# PC.net
KiCad netlist of a schematic drawn in EAGLE
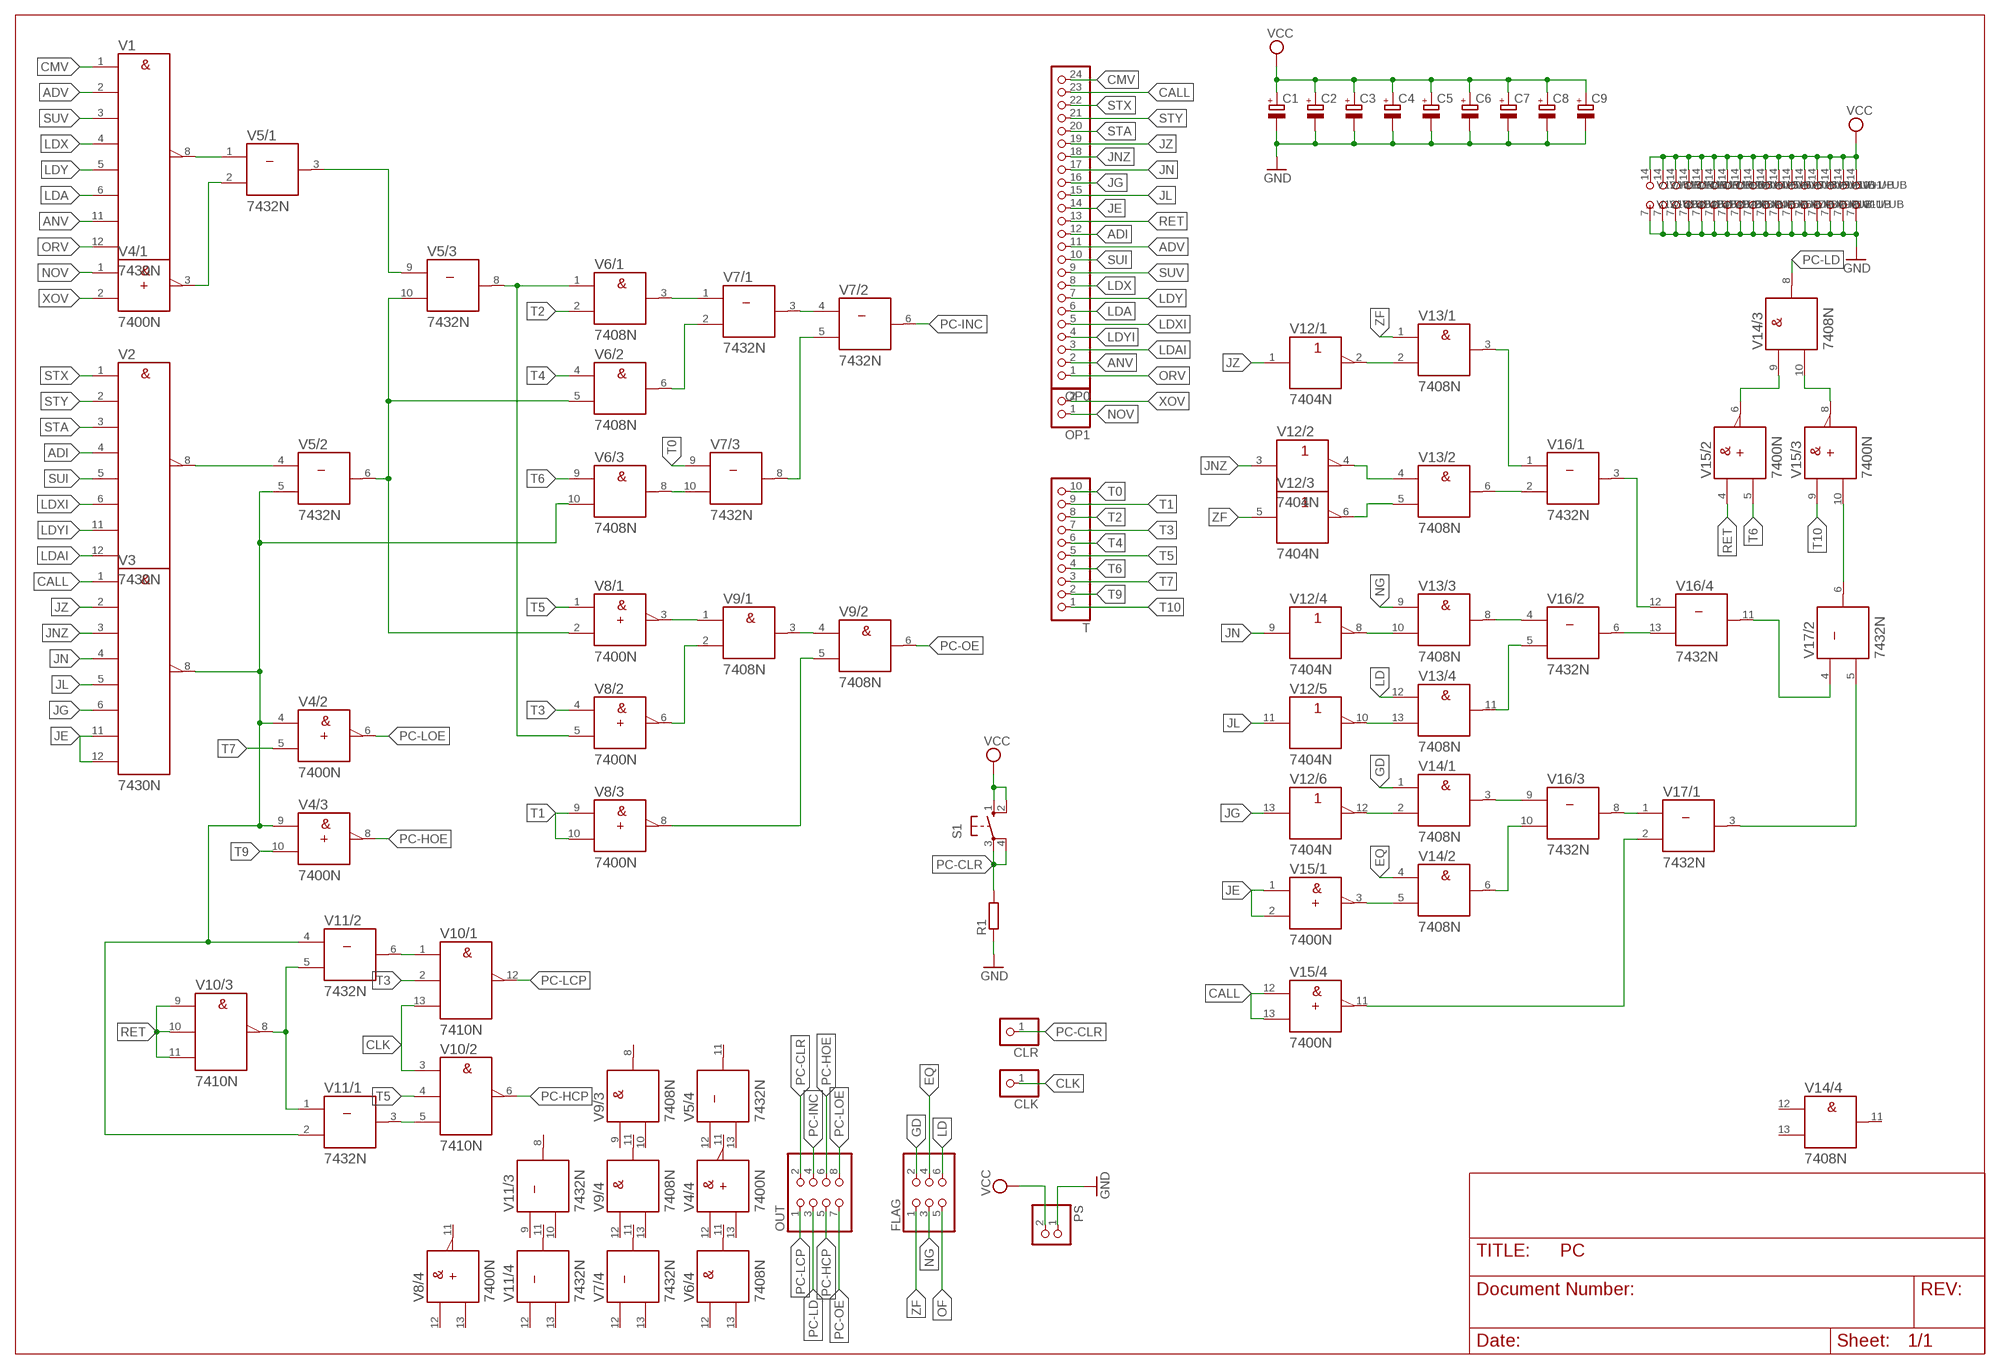
[diagram p0: schematic, sheet 1]

(export (version "E")
  (design (tool "Eeschema 10.0.6"))
  (components
    (comp (ref "C1")
      (value "CPOL-EUE2.5-6")
      (footprint "eagle-import:E2,5-6")
      (libsource (lib "eagle-import") (part "CPOL-EUE2.5-6"))
    )
    (comp (ref "C2")
      (value "CPOL-EUE2.5-6")
      (footprint "eagle-import:E2,5-6")
      (libsource (lib "eagle-import") (part "CPOL-EUE2.5-6"))
    )
    (comp (ref "C3")
      (value "CPOL-EUE2.5-6")
      (footprint "eagle-import:E2,5-6")
      (libsource (lib "eagle-import") (part "CPOL-EUE2.5-6"))
    )
    (comp (ref "C4")
      (value "CPOL-EUE2.5-6")
      (footprint "eagle-import:E2,5-6")
      (libsource (lib "eagle-import") (part "CPOL-EUE2.5-6"))
    )
    (comp (ref "C5")
      (value "CPOL-EUE2.5-6")
      (footprint "eagle-import:E2,5-6")
      (libsource (lib "eagle-import") (part "CPOL-EUE2.5-6"))
    )
    (comp (ref "C6")
      (value "CPOL-EUE2.5-6")
      (footprint "eagle-import:E2,5-6")
      (libsource (lib "eagle-import") (part "CPOL-EUE2.5-6"))
    )
    (comp (ref "C7")
      (value "CPOL-EUE2.5-6")
      (footprint "eagle-import:E2,5-6")
      (libsource (lib "eagle-import") (part "CPOL-EUE2.5-6"))
    )
    (comp (ref "C8")
      (value "CPOL-EUE2.5-6")
      (footprint "eagle-import:E2,5-6")
      (libsource (lib "eagle-import") (part "CPOL-EUE2.5-6"))
    )
    (comp (ref "C9")
      (value "CPOL-EUE2.5-6")
      (footprint "eagle-import:E2,5-6")
      (libsource (lib "eagle-import") (part "CPOL-EUE2.5-6"))
    )
    (comp (ref "CLK")
      (value "PINHD-1X1")
      (footprint "eagle-import:1X01")
      (libsource (lib "eagle-import") (part "PINHD-1X1"))
    )
    (comp (ref "CLR")
      (value "PINHD-1X1")
      (footprint "eagle-import:1X01")
      (libsource (lib "eagle-import") (part "PINHD-1X1"))
    )
    (comp (ref "FLAG")
      (value "PINHD-2X3")
      (footprint "eagle-import:2X03")
      (libsource (lib "eagle-import") (part "PINHD-2X3"))
    )
    (comp (ref "OP0")
      (value "PINHD-1X24")
      (footprint "eagle-import:1X24")
      (libsource (lib "eagle-import") (part "PINHD-1X24"))
    )
    (comp (ref "OP1")
      (value "PINHD-1X2")
      (footprint "eagle-import:1X02")
      (libsource (lib "eagle-import") (part "PINHD-1X2"))
    )
    (comp (ref "OUT")
      (value "PINHD-2X4")
      (footprint "eagle-import:2X04")
      (libsource (lib "eagle-import") (part "PINHD-2X4"))
    )
    (comp (ref "PS")
      (value "PINHD-1X2")
      (footprint "eagle-import:1X02")
      (libsource (lib "eagle-import") (part "PINHD-1X2"))
    )
    (comp (ref "R1")
      (value "R-EU_0207/7")
      (footprint "eagle-import:0207_7")
      (libsource (lib "eagle-import") (part "R-EU_0207/7"))
    )
    (comp (ref "S1")
      (value "10-XX")
      (footprint "eagle-import:B3F-10XX")
      (fields (field (name "MPN") "B3F-1000"))
      (libsource (lib "eagle-import") (part "10-XX"))
    )
    (comp (ref "T")
      (value "PINHD-1X10")
      (footprint "eagle-import:1X10")
      (libsource (lib "eagle-import") (part "PINHD-1X10"))
    )
    (comp (ref "V1")
      (value "7430N")
      (footprint "eagle-import:DIL14")
      (libsource (lib "eagle-import") (part "7430N"))
    )
    (comp (ref "V2")
      (value "7430N")
      (footprint "eagle-import:DIL14")
      (libsource (lib "eagle-import") (part "7430N"))
    )
    (comp (ref "V3")
      (value "7430N")
      (footprint "eagle-import:DIL14")
      (libsource (lib "eagle-import") (part "7430N"))
    )
    (comp (ref "V4")
      (value "7400N")
      (footprint "eagle-import:DIL14")
      (libsource (lib "eagle-import") (part "7400N"))
    )
    (comp (ref "V5")
      (value "7432N")
      (footprint "eagle-import:DIL14")
      (libsource (lib "eagle-import") (part "7432N"))
    )
    (comp (ref "V6")
      (value "7408N")
      (footprint "eagle-import:DIL14")
      (libsource (lib "eagle-import") (part "7408N"))
    )
    (comp (ref "V7")
      (value "7432N")
      (footprint "eagle-import:DIL14")
      (libsource (lib "eagle-import") (part "7432N"))
    )
    (comp (ref "V8")
      (value "7400N")
      (footprint "eagle-import:DIL14")
      (libsource (lib "eagle-import") (part "7400N"))
    )
    (comp (ref "V9")
      (value "7408N")
      (footprint "eagle-import:DIL14")
      (libsource (lib "eagle-import") (part "7408N"))
    )
    (comp (ref "V10")
      (value "7410N")
      (footprint "eagle-import:DIL14")
      (libsource (lib "eagle-import") (part "7410N"))
    )
    (comp (ref "V11")
      (value "7432N")
      (footprint "eagle-import:DIL14")
      (libsource (lib "eagle-import") (part "7432N"))
    )
    (comp (ref "V12")
      (value "7404N")
      (footprint "eagle-import:DIL14")
      (libsource (lib "eagle-import") (part "7404N"))
    )
    (comp (ref "V13")
      (value "7408N")
      (footprint "eagle-import:DIL14")
      (libsource (lib "eagle-import") (part "7408N"))
    )
    (comp (ref "V14")
      (value "7408N")
      (footprint "eagle-import:DIL14")
      (libsource (lib "eagle-import") (part "7408N"))
    )
    (comp (ref "V15")
      (value "7400N")
      (footprint "eagle-import:DIL14")
      (libsource (lib "eagle-import") (part "7400N"))
    )
    (comp (ref "V16")
      (value "7432N")
      (footprint "eagle-import:DIL14")
      (libsource (lib "eagle-import") (part "7432N"))
    )
    (comp (ref "V17")
      (value "7432N")
      (footprint "eagle-import:DIL14")
      (libsource (lib "eagle-import") (part "7432N"))
    )
  )
  (nets
    (net (code "1") (name "ADI") (class "Default")
      (node (ref "OP0") (pin "12") (pinfunction "12_12") (pintype "passive"))
      (node (ref "V2") (pin "4") (pinfunction "D_4") (pintype "input"))
    )
    (net (code "2") (name "ADV") (class "Default")
      (node (ref "OP0") (pin "11") (pinfunction "11_11") (pintype "passive"))
      (node (ref "V1") (pin "2") (pinfunction "B_2") (pintype "input"))
    )
    (net (code "3") (name "ANV") (class "Default")
      (node (ref "OP0") (pin "2") (pinfunction "2_2") (pintype "passive"))
      (node (ref "V1") (pin "11") (pinfunction "G_11") (pintype "input"))
    )
    (net (code "4") (name "CALL") (class "Default")
      (node (ref "OP0") (pin "23") (pinfunction "23_23") (pintype "passive"))
      (node (ref "V15") (pin "12") (pinfunction "A_12") (pintype "input"))
      (node (ref "V15") (pin "13") (pinfunction "B_13") (pintype "input"))
      (node (ref "V3") (pin "1") (pinfunction "A_1") (pintype "input"))
    )
    (net (code "5") (name "CLK") (class "Default")
      (node (ref "CLK") (pin "1") (pinfunction "1_1") (pintype "passive"))
      (node (ref "V10") (pin "13") (pinfunction "C_13") (pintype "input"))
      (node (ref "V10") (pin "3") (pinfunction "A_3") (pintype "input"))
    )
    (net (code "6") (name "CMV") (class "Default")
      (node (ref "OP0") (pin "24") (pinfunction "24_24") (pintype "passive"))
      (node (ref "V1") (pin "1") (pinfunction "A_1") (pintype "input"))
    )
    (net (code "7") (name "EQ") (class "Default")
      (node (ref "FLAG") (pin "4") (pinfunction "4_4") (pintype "passive"))
      (node (ref "V14") (pin "4") (pinfunction "A_4") (pintype "input"))
    )
    (net (code "8") (name "GD") (class "Default")
      (node (ref "FLAG") (pin "2") (pinfunction "2_2") (pintype "passive"))
      (node (ref "V14") (pin "1") (pinfunction "A_1") (pintype "input"))
    )
    (net (code "9") (name "GND") (class "Default")
      (node (ref "C1") (pin "-") (pinfunction "-_-") (pintype "passive"))
      (node (ref "C2") (pin "-") (pinfunction "-_-") (pintype "passive"))
      (node (ref "C3") (pin "-") (pinfunction "-_-") (pintype "passive"))
      (node (ref "C4") (pin "-") (pinfunction "-_-") (pintype "passive"))
      (node (ref "C5") (pin "-") (pinfunction "-_-") (pintype "passive"))
      (node (ref "C6") (pin "-") (pinfunction "-_-") (pintype "passive"))
      (node (ref "C7") (pin "-") (pinfunction "-_-") (pintype "passive"))
      (node (ref "C8") (pin "-") (pinfunction "-_-") (pintype "passive"))
      (node (ref "C9") (pin "-") (pinfunction "-_-") (pintype "passive"))
      (node (ref "PS") (pin "1") (pinfunction "1_1") (pintype "passive"))
      (node (ref "R1") (pin "1") (pinfunction "1_1") (pintype "passive"))
      (node (ref "V1") (pin "7") (pinfunction "-UB_7") (pintype "power_in"))
      (node (ref "V10") (pin "7") (pinfunction "-UB_7") (pintype "power_in"))
      (node (ref "V11") (pin "7") (pinfunction "-UB_7") (pintype "power_in"))
      (node (ref "V12") (pin "7") (pinfunction "-UB_7") (pintype "power_in"))
      (node (ref "V13") (pin "7") (pinfunction "-UB_7") (pintype "power_in"))
      (node (ref "V14") (pin "7") (pinfunction "-UB_7") (pintype "power_in"))
      (node (ref "V15") (pin "7") (pinfunction "-UB_7") (pintype "power_in"))
      (node (ref "V16") (pin "7") (pinfunction "-UB_7") (pintype "power_in"))
      (node (ref "V17") (pin "7") (pinfunction "-UB_7") (pintype "power_in"))
      (node (ref "V2") (pin "7") (pinfunction "-UB_7") (pintype "power_in"))
      (node (ref "V3") (pin "7") (pinfunction "-UB_7") (pintype "power_in"))
      (node (ref "V4") (pin "7") (pinfunction "-UB_7") (pintype "power_in"))
      (node (ref "V5") (pin "7") (pinfunction "-UB_7") (pintype "power_in"))
      (node (ref "V6") (pin "7") (pinfunction "-UB_7") (pintype "power_in"))
      (node (ref "V7") (pin "7") (pinfunction "-UB_7") (pintype "power_in"))
      (node (ref "V8") (pin "7") (pinfunction "-UB_7") (pintype "power_in"))
      (node (ref "V9") (pin "7") (pinfunction "-UB_7") (pintype "power_in"))
    )
    (net (code "10") (name "JE") (class "Default")
      (node (ref "OP0") (pin "14") (pinfunction "14_14") (pintype "passive"))
      (node (ref "V15") (pin "1") (pinfunction "A_1") (pintype "input"))
      (node (ref "V15") (pin "2") (pinfunction "B_2") (pintype "input"))
      (node (ref "V3") (pin "11") (pinfunction "G_11") (pintype "input"))
      (node (ref "V3") (pin "12") (pinfunction "H_12") (pintype "input"))
    )
    (net (code "11") (name "JG") (class "Default")
      (node (ref "OP0") (pin "16") (pinfunction "16_16") (pintype "passive"))
      (node (ref "V12") (pin "13") (pinfunction "A_13") (pintype "input"))
      (node (ref "V3") (pin "6") (pinfunction "F_6") (pintype "input"))
    )
    (net (code "12") (name "JL") (class "Default")
      (node (ref "OP0") (pin "15") (pinfunction "15_15") (pintype "passive"))
      (node (ref "V12") (pin "11") (pinfunction "A_11") (pintype "input"))
      (node (ref "V3") (pin "5") (pinfunction "E_5") (pintype "input"))
    )
    (net (code "13") (name "JN") (class "Default")
      (node (ref "OP0") (pin "17") (pinfunction "17_17") (pintype "passive"))
      (node (ref "V12") (pin "9") (pinfunction "A_9") (pintype "input"))
      (node (ref "V3") (pin "4") (pinfunction "D_4") (pintype "input"))
    )
    (net (code "14") (name "JNZ") (class "Default")
      (node (ref "OP0") (pin "18") (pinfunction "18_18") (pintype "passive"))
      (node (ref "V12") (pin "3") (pinfunction "A_3") (pintype "input"))
      (node (ref "V3") (pin "3") (pinfunction "C_3") (pintype "input"))
    )
    (net (code "15") (name "JZ") (class "Default")
      (node (ref "OP0") (pin "19") (pinfunction "19_19") (pintype "passive"))
      (node (ref "V12") (pin "1") (pinfunction "A_1") (pintype "input"))
      (node (ref "V3") (pin "2") (pinfunction "B_2") (pintype "input"))
    )
    (net (code "16") (name "LD") (class "Default")
      (node (ref "FLAG") (pin "6") (pinfunction "6_6") (pintype "passive"))
      (node (ref "V13") (pin "12") (pinfunction "A_12") (pintype "input"))
    )
    (net (code "17") (name "LDA") (class "Default")
      (node (ref "OP0") (pin "6") (pinfunction "6_6") (pintype "passive"))
      (node (ref "V1") (pin "6") (pinfunction "F_6") (pintype "input"))
    )
    (net (code "18") (name "LDAI") (class "Default")
      (node (ref "OP0") (pin "3") (pinfunction "3_3") (pintype "passive"))
      (node (ref "V2") (pin "12") (pinfunction "H_12") (pintype "input"))
    )
    (net (code "19") (name "LDX") (class "Default")
      (node (ref "OP0") (pin "8") (pinfunction "8_8") (pintype "passive"))
      (node (ref "V1") (pin "4") (pinfunction "D_4") (pintype "input"))
    )
    (net (code "20") (name "LDXI") (class "Default")
      (node (ref "OP0") (pin "5") (pinfunction "5_5") (pintype "passive"))
      (node (ref "V2") (pin "6") (pinfunction "F_6") (pintype "input"))
    )
    (net (code "21") (name "LDY") (class "Default")
      (node (ref "OP0") (pin "7") (pinfunction "7_7") (pintype "passive"))
      (node (ref "V1") (pin "5") (pinfunction "E_5") (pintype "input"))
    )
    (net (code "22") (name "LDYI") (class "Default")
      (node (ref "OP0") (pin "4") (pinfunction "4_4") (pintype "passive"))
      (node (ref "V2") (pin "11") (pinfunction "G_11") (pintype "input"))
    )
    (net (code "23") (name "NG") (class "Default")
      (node (ref "FLAG") (pin "3") (pinfunction "3_3") (pintype "passive"))
      (node (ref "V13") (pin "9") (pinfunction "A_9") (pintype "input"))
    )
    (net (code "24") (name "NOV") (class "Default")
      (node (ref "OP1") (pin "1") (pinfunction "1_1") (pintype "passive"))
      (node (ref "V4") (pin "1") (pinfunction "A_1") (pintype "input"))
    )
    (net (code "25") (name "Net-(V1C-Y)") (class "Default")
      (node (ref "V1") (pin "8") (pinfunction "Y_8") (pintype "output"))
      (node (ref "V5") (pin "1") (pinfunction "A_1") (pintype "input"))
    )
    (net (code "26") (name "Net-(V2C-Y)") (class "Default")
      (node (ref "V2") (pin "8") (pinfunction "Y_8") (pintype "output"))
      (node (ref "V5") (pin "4") (pinfunction "A_4") (pintype "input"))
    )
    (net (code "27") (name "Net-(V4C-Y)") (class "Default")
      (node (ref "V4") (pin "3") (pinfunction "Y_3") (pintype "output"))
      (node (ref "V5") (pin "2") (pinfunction "B_2") (pintype "input"))
    )
    (net (code "28") (name "Net-(V5C-Y)") (class "Default")
      (node (ref "V5") (pin "3") (pinfunction "Y_3") (pintype "output"))
      (node (ref "V5") (pin "9") (pinfunction "A_9") (pintype "input"))
    )
    (net (code "29") (name "Net-(V5D-Y)") (class "Default")
      (node (ref "V5") (pin "10") (pinfunction "B_10") (pintype "input"))
      (node (ref "V5") (pin "6") (pinfunction "Y_6") (pintype "output"))
      (node (ref "V6") (pin "5") (pinfunction "B_5") (pintype "input"))
      (node (ref "V8") (pin "2") (pinfunction "B_2") (pintype "input"))
    )
    (net (code "30") (name "Net-(V5E-Y)") (class "Default")
      (node (ref "V5") (pin "8") (pinfunction "Y_8") (pintype "output"))
      (node (ref "V6") (pin "1") (pinfunction "A_1") (pintype "input"))
      (node (ref "V8") (pin "5") (pinfunction "B_5") (pintype "input"))
    )
    (net (code "31") (name "Net-(V6C-Y)") (class "Default")
      (node (ref "V6") (pin "3") (pinfunction "Y_3") (pintype "output"))
      (node (ref "V7") (pin "1") (pinfunction "A_1") (pintype "input"))
    )
    (net (code "32") (name "Net-(V6D-Y)") (class "Default")
      (node (ref "V6") (pin "6") (pinfunction "Y_6") (pintype "output"))
      (node (ref "V7") (pin "2") (pinfunction "B_2") (pintype "input"))
    )
    (net (code "33") (name "Net-(V6E-Y)") (class "Default")
      (node (ref "V6") (pin "8") (pinfunction "Y_8") (pintype "output"))
      (node (ref "V7") (pin "10") (pinfunction "B_10") (pintype "input"))
    )
    (net (code "34") (name "Net-(V7C-Y)") (class "Default")
      (node (ref "V7") (pin "3") (pinfunction "Y_3") (pintype "output"))
      (node (ref "V7") (pin "4") (pinfunction "A_4") (pintype "input"))
    )
    (net (code "35") (name "Net-(V7D-B)") (class "Default")
      (node (ref "V7") (pin "5") (pinfunction "B_5") (pintype "input"))
      (node (ref "V7") (pin "8") (pinfunction "Y_8") (pintype "output"))
    )
    (net (code "36") (name "Net-(V8C-Y)") (class "Default")
      (node (ref "V8") (pin "3") (pinfunction "Y_3") (pintype "output"))
      (node (ref "V9") (pin "1") (pinfunction "A_1") (pintype "input"))
    )
    (net (code "37") (name "Net-(V8D-Y)") (class "Default")
      (node (ref "V8") (pin "6") (pinfunction "Y_6") (pintype "output"))
      (node (ref "V9") (pin "2") (pinfunction "B_2") (pintype "input"))
    )
    (net (code "38") (name "Net-(V8E-Y)") (class "Default")
      (node (ref "V8") (pin "8") (pinfunction "Y_8") (pintype "output"))
      (node (ref "V9") (pin "5") (pinfunction "B_5") (pintype "input"))
    )
    (net (code "39") (name "Net-(V9C-Y)") (class "Default")
      (node (ref "V9") (pin "3") (pinfunction "Y_3") (pintype "output"))
      (node (ref "V9") (pin "4") (pinfunction "A_4") (pintype "input"))
    )
    (net (code "40") (name "Net-(V10C-A)") (class "Default")
      (node (ref "V10") (pin "1") (pinfunction "A_1") (pintype "input"))
      (node (ref "V11") (pin "6") (pinfunction "Y_6") (pintype "output"))
    )
    (net (code "41") (name "Net-(V10D-C)") (class "Default")
      (node (ref "V10") (pin "5") (pinfunction "C_5") (pintype "input"))
      (node (ref "V11") (pin "3") (pinfunction "Y_3") (pintype "output"))
    )
    (net (code "42") (name "Net-(V10E-Y)") (class "Default")
      (node (ref "V10") (pin "8") (pinfunction "Y_8") (pintype "output"))
      (node (ref "V11") (pin "1") (pinfunction "A_1") (pintype "input"))
      (node (ref "V11") (pin "5") (pinfunction "B_5") (pintype "input"))
    )
    (net (code "43") (name "Net-(V11C-B)") (class "Default")
      (node (ref "V11") (pin "2") (pinfunction "B_2") (pintype "input"))
      (node (ref "V11") (pin "4") (pinfunction "A_4") (pintype "input"))
      (node (ref "V3") (pin "8") (pinfunction "Y_8") (pintype "output"))
      (node (ref "V4") (pin "4") (pinfunction "A_4") (pintype "input"))
      (node (ref "V4") (pin "9") (pinfunction "A_9") (pintype "input"))
      (node (ref "V5") (pin "5") (pinfunction "B_5") (pintype "input"))
      (node (ref "V6") (pin "10") (pinfunction "B_10") (pintype "input"))
    )
    (net (code "44") (name "Net-(V12C-Y)") (class "Default")
      (node (ref "V12") (pin "2") (pinfunction "Y_2") (pintype "output"))
      (node (ref "V13") (pin "2") (pinfunction "B_2") (pintype "input"))
    )
    (net (code "45") (name "Net-(V12D-Y)") (class "Default")
      (node (ref "V12") (pin "4") (pinfunction "Y_4") (pintype "output"))
      (node (ref "V13") (pin "4") (pinfunction "A_4") (pintype "input"))
    )
    (net (code "46") (name "Net-(V12E-Y)") (class "Default")
      (node (ref "V12") (pin "6") (pinfunction "Y_6") (pintype "output"))
      (node (ref "V13") (pin "5") (pinfunction "B_5") (pintype "input"))
    )
    (net (code "47") (name "Net-(V12F-Y)") (class "Default")
      (node (ref "V12") (pin "8") (pinfunction "Y_8") (pintype "output"))
      (node (ref "V13") (pin "10") (pinfunction "B_10") (pintype "input"))
    )
    (net (code "48") (name "Net-(V12G-Y)") (class "Default")
      (node (ref "V12") (pin "10") (pinfunction "Y_10") (pintype "output"))
      (node (ref "V13") (pin "13") (pinfunction "B_13") (pintype "input"))
    )
    (net (code "49") (name "Net-(V12H-Y)") (class "Default")
      (node (ref "V12") (pin "12") (pinfunction "Y_12") (pintype "output"))
      (node (ref "V14") (pin "2") (pinfunction "B_2") (pintype "input"))
    )
    (net (code "50") (name "Net-(V13C-Y)") (class "Default")
      (node (ref "V13") (pin "3") (pinfunction "Y_3") (pintype "output"))
      (node (ref "V16") (pin "1") (pinfunction "A_1") (pintype "input"))
    )
    (net (code "51") (name "Net-(V13D-Y)") (class "Default")
      (node (ref "V13") (pin "6") (pinfunction "Y_6") (pintype "output"))
      (node (ref "V16") (pin "2") (pinfunction "B_2") (pintype "input"))
    )
    (net (code "52") (name "Net-(V13E-Y)") (class "Default")
      (node (ref "V13") (pin "8") (pinfunction "Y_8") (pintype "output"))
      (node (ref "V16") (pin "4") (pinfunction "A_4") (pintype "input"))
    )
    (net (code "53") (name "Net-(V13F-Y)") (class "Default")
      (node (ref "V13") (pin "11") (pinfunction "Y_11") (pintype "output"))
      (node (ref "V16") (pin "5") (pinfunction "B_5") (pintype "input"))
    )
    (net (code "54") (name "Net-(V14C-Y)") (class "Default")
      (node (ref "V14") (pin "3") (pinfunction "Y_3") (pintype "output"))
      (node (ref "V16") (pin "9") (pinfunction "A_9") (pintype "input"))
    )
    (net (code "55") (name "Net-(V14D-B)") (class "Default")
      (node (ref "V14") (pin "5") (pinfunction "B_5") (pintype "input"))
      (node (ref "V15") (pin "3") (pinfunction "Y_3") (pintype "output"))
    )
    (net (code "56") (name "Net-(V14D-Y)") (class "Default")
      (node (ref "V14") (pin "6") (pinfunction "Y_6") (pintype "output"))
      (node (ref "V16") (pin "10") (pinfunction "B_10") (pintype "input"))
    )
    (net (code "57") (name "Net-(V14E-A)") (class "Default")
      (node (ref "V14") (pin "9") (pinfunction "A_9") (pintype "input"))
      (node (ref "V15") (pin "6") (pinfunction "Y_6") (pintype "output"))
    )
    (net (code "58") (name "Net-(V14E-B)") (class "Default")
      (node (ref "V14") (pin "10") (pinfunction "B_10") (pintype "input"))
      (node (ref "V15") (pin "8") (pinfunction "Y_8") (pintype "output"))
    )
    (net (code "59") (name "Net-(V15E-B)") (class "Default")
      (node (ref "V15") (pin "10") (pinfunction "B_10") (pintype "input"))
      (node (ref "V17") (pin "6") (pinfunction "Y_6") (pintype "output"))
    )
    (net (code "60") (name "Net-(V15F-Y)") (class "Default")
      (node (ref "V15") (pin "11") (pinfunction "Y_11") (pintype "output"))
      (node (ref "V17") (pin "2") (pinfunction "B_2") (pintype "input"))
    )
    (net (code "61") (name "Net-(V16C-Y)") (class "Default")
      (node (ref "V16") (pin "12") (pinfunction "A_12") (pintype "input"))
      (node (ref "V16") (pin "3") (pinfunction "Y_3") (pintype "output"))
    )
    (net (code "62") (name "Net-(V16D-Y)") (class "Default")
      (node (ref "V16") (pin "13") (pinfunction "B_13") (pintype "input"))
      (node (ref "V16") (pin "6") (pinfunction "Y_6") (pintype "output"))
    )
    (net (code "63") (name "Net-(V16E-Y)") (class "Default")
      (node (ref "V16") (pin "8") (pinfunction "Y_8") (pintype "output"))
      (node (ref "V17") (pin "1") (pinfunction "A_1") (pintype "input"))
    )
    (net (code "64") (name "Net-(V16F-Y)") (class "Default")
      (node (ref "V16") (pin "11") (pinfunction "Y_11") (pintype "output"))
      (node (ref "V17") (pin "4") (pinfunction "A_4") (pintype "input"))
    )
    (net (code "65") (name "Net-(V17C-Y)") (class "Default")
      (node (ref "V17") (pin "3") (pinfunction "Y_3") (pintype "output"))
      (node (ref "V17") (pin "5") (pinfunction "B_5") (pintype "input"))
    )
    (net (code "66") (name "OF") (class "Default")
      (node (ref "FLAG") (pin "5") (pinfunction "5_5") (pintype "passive"))
    )
    (net (code "67") (name "ORV") (class "Default")
      (node (ref "OP0") (pin "1") (pinfunction "1_1") (pintype "passive"))
      (node (ref "V1") (pin "12") (pinfunction "H_12") (pintype "input"))
    )
    (net (code "68") (name "PC-CLR") (class "Default")
      (node (ref "CLR") (pin "1") (pinfunction "1_1") (pintype "passive"))
      (node (ref "OUT") (pin "2") (pinfunction "2_2") (pintype "passive"))
      (node (ref "R1") (pin "2") (pinfunction "2_2") (pintype "passive"))
      (node (ref "S1") (pin "3") (pinfunction "P_3") (pintype "passive"))
      (node (ref "S1") (pin "4") (pinfunction "P1_4") (pintype "passive"))
    )
    (net (code "69") (name "PC-HCP") (class "Default")
      (node (ref "OUT") (pin "5") (pinfunction "5_5") (pintype "passive"))
      (node (ref "V10") (pin "6") (pinfunction "Y_6") (pintype "output"))
    )
    (net (code "70") (name "PC-HOE") (class "Default")
      (node (ref "OUT") (pin "6") (pinfunction "6_6") (pintype "passive"))
      (node (ref "V4") (pin "8") (pinfunction "Y_8") (pintype "output"))
    )
    (net (code "71") (name "PC-INC") (class "Default")
      (node (ref "OUT") (pin "4") (pinfunction "4_4") (pintype "passive"))
      (node (ref "V7") (pin "6") (pinfunction "Y_6") (pintype "output"))
    )
    (net (code "72") (name "PC-LCP") (class "Default")
      (node (ref "OUT") (pin "1") (pinfunction "1_1") (pintype "passive"))
      (node (ref "V10") (pin "12") (pinfunction "Y_12") (pintype "output"))
    )
    (net (code "73") (name "PC-LD") (class "Default")
      (node (ref "OUT") (pin "3") (pinfunction "3_3") (pintype "passive"))
      (node (ref "V14") (pin "8") (pinfunction "Y_8") (pintype "output"))
    )
    (net (code "74") (name "PC-LOE") (class "Default")
      (node (ref "OUT") (pin "8") (pinfunction "8_8") (pintype "passive"))
      (node (ref "V4") (pin "6") (pinfunction "Y_6") (pintype "output"))
    )
    (net (code "75") (name "PC-OE") (class "Default")
      (node (ref "OUT") (pin "7") (pinfunction "7_7") (pintype "passive"))
      (node (ref "V9") (pin "6") (pinfunction "Y_6") (pintype "output"))
    )
    (net (code "76") (name "RET") (class "Default")
      (node (ref "OP0") (pin "13") (pinfunction "13_13") (pintype "passive"))
      (node (ref "V10") (pin "10") (pinfunction "B_10") (pintype "input"))
      (node (ref "V10") (pin "11") (pinfunction "C_11") (pintype "input"))
      (node (ref "V10") (pin "9") (pinfunction "A_9") (pintype "input"))
      (node (ref "V15") (pin "4") (pinfunction "A_4") (pintype "input"))
    )
    (net (code "77") (name "STA") (class "Default")
      (node (ref "OP0") (pin "20") (pinfunction "20_20") (pintype "passive"))
      (node (ref "V2") (pin "3") (pinfunction "C_3") (pintype "input"))
    )
    (net (code "78") (name "STX") (class "Default")
      (node (ref "OP0") (pin "22") (pinfunction "22_22") (pintype "passive"))
      (node (ref "V2") (pin "1") (pinfunction "A_1") (pintype "input"))
    )
    (net (code "79") (name "STY") (class "Default")
      (node (ref "OP0") (pin "21") (pinfunction "21_21") (pintype "passive"))
      (node (ref "V2") (pin "2") (pinfunction "B_2") (pintype "input"))
    )
    (net (code "80") (name "SUI") (class "Default")
      (node (ref "OP0") (pin "10") (pinfunction "10_10") (pintype "passive"))
      (node (ref "V2") (pin "5") (pinfunction "E_5") (pintype "input"))
    )
    (net (code "81") (name "SUV") (class "Default")
      (node (ref "OP0") (pin "9") (pinfunction "9_9") (pintype "passive"))
      (node (ref "V1") (pin "3") (pinfunction "C_3") (pintype "input"))
    )
    (net (code "82") (name "T0") (class "Default")
      (node (ref "T") (pin "10") (pinfunction "10_10") (pintype "passive"))
      (node (ref "V7") (pin "9") (pinfunction "A_9") (pintype "input"))
    )
    (net (code "83") (name "T1") (class "Default")
      (node (ref "T") (pin "9") (pinfunction "9_9") (pintype "passive"))
      (node (ref "V8") (pin "10") (pinfunction "B_10") (pintype "input"))
      (node (ref "V8") (pin "9") (pinfunction "A_9") (pintype "input"))
    )
    (net (code "84") (name "T2") (class "Default")
      (node (ref "T") (pin "8") (pinfunction "8_8") (pintype "passive"))
      (node (ref "V6") (pin "2") (pinfunction "B_2") (pintype "input"))
    )
    (net (code "85") (name "T3") (class "Default")
      (node (ref "T") (pin "7") (pinfunction "7_7") (pintype "passive"))
      (node (ref "V10") (pin "2") (pinfunction "B_2") (pintype "input"))
      (node (ref "V8") (pin "4") (pinfunction "A_4") (pintype "input"))
    )
    (net (code "86") (name "T4") (class "Default")
      (node (ref "T") (pin "6") (pinfunction "6_6") (pintype "passive"))
      (node (ref "V6") (pin "4") (pinfunction "A_4") (pintype "input"))
    )
    (net (code "87") (name "T5") (class "Default")
      (node (ref "T") (pin "5") (pinfunction "5_5") (pintype "passive"))
      (node (ref "V10") (pin "4") (pinfunction "B_4") (pintype "input"))
      (node (ref "V8") (pin "1") (pinfunction "A_1") (pintype "input"))
    )
    (net (code "88") (name "T6") (class "Default")
      (node (ref "T") (pin "4") (pinfunction "4_4") (pintype "passive"))
      (node (ref "V15") (pin "5") (pinfunction "B_5") (pintype "input"))
      (node (ref "V6") (pin "9") (pinfunction "A_9") (pintype "input"))
    )
    (net (code "89") (name "T7") (class "Default")
      (node (ref "T") (pin "3") (pinfunction "3_3") (pintype "passive"))
      (node (ref "V4") (pin "5") (pinfunction "B_5") (pintype "input"))
    )
    (net (code "90") (name "T9") (class "Default")
      (node (ref "T") (pin "2") (pinfunction "2_2") (pintype "passive"))
      (node (ref "V4") (pin "10") (pinfunction "B_10") (pintype "input"))
    )
    (net (code "91") (name "T10") (class "Default")
      (node (ref "T") (pin "1") (pinfunction "1_1") (pintype "passive"))
      (node (ref "V15") (pin "9") (pinfunction "A_9") (pintype "input"))
    )
    (net (code "92") (name "VCC") (class "Default")
      (node (ref "C1") (pin "+") (pinfunction "+_+") (pintype "passive"))
      (node (ref "C2") (pin "+") (pinfunction "+_+") (pintype "passive"))
      (node (ref "C3") (pin "+") (pinfunction "+_+") (pintype "passive"))
      (node (ref "C4") (pin "+") (pinfunction "+_+") (pintype "passive"))
      (node (ref "C5") (pin "+") (pinfunction "+_+") (pintype "passive"))
      (node (ref "C6") (pin "+") (pinfunction "+_+") (pintype "passive"))
      (node (ref "C7") (pin "+") (pinfunction "+_+") (pintype "passive"))
      (node (ref "C8") (pin "+") (pinfunction "+_+") (pintype "passive"))
      (node (ref "C9") (pin "+") (pinfunction "+_+") (pintype "passive"))
      (node (ref "PS") (pin "2") (pinfunction "2_2") (pintype "passive"))
      (node (ref "S1") (pin "1") (pinfunction "S_1") (pintype "passive"))
      (node (ref "S1") (pin "2") (pinfunction "S1_2") (pintype "passive"))
      (node (ref "V1") (pin "14") (pinfunction "+UB_14") (pintype "power_in"))
      (node (ref "V10") (pin "14") (pinfunction "+UB_14") (pintype "power_in"))
      (node (ref "V11") (pin "14") (pinfunction "+UB_14") (pintype "power_in"))
      (node (ref "V12") (pin "14") (pinfunction "+UB_14") (pintype "power_in"))
      (node (ref "V13") (pin "14") (pinfunction "+UB_14") (pintype "power_in"))
      (node (ref "V14") (pin "14") (pinfunction "+UB_14") (pintype "power_in"))
      (node (ref "V15") (pin "14") (pinfunction "+UB_14") (pintype "power_in"))
      (node (ref "V16") (pin "14") (pinfunction "+UB_14") (pintype "power_in"))
      (node (ref "V17") (pin "14") (pinfunction "+UB_14") (pintype "power_in"))
      (node (ref "V2") (pin "14") (pinfunction "+UB_14") (pintype "power_in"))
      (node (ref "V3") (pin "14") (pinfunction "+UB_14") (pintype "power_in"))
      (node (ref "V4") (pin "14") (pinfunction "+UB_14") (pintype "power_in"))
      (node (ref "V5") (pin "14") (pinfunction "+UB_14") (pintype "power_in"))
      (node (ref "V6") (pin "14") (pinfunction "+UB_14") (pintype "power_in"))
      (node (ref "V7") (pin "14") (pinfunction "+UB_14") (pintype "power_in"))
      (node (ref "V8") (pin "14") (pinfunction "+UB_14") (pintype "power_in"))
      (node (ref "V9") (pin "14") (pinfunction "+UB_14") (pintype "power_in"))
    )
    (net (code "93") (name "XOV") (class "Default")
      (node (ref "OP1") (pin "2") (pinfunction "2_2") (pintype "passive"))
      (node (ref "V4") (pin "2") (pinfunction "B_2") (pintype "input"))
    )
    (net (code "94") (name "ZF") (class "Default")
      (node (ref "FLAG") (pin "1") (pinfunction "1_1") (pintype "passive"))
      (node (ref "V12") (pin "5") (pinfunction "A_5") (pintype "input"))
      (node (ref "V13") (pin "1") (pinfunction "A_1") (pintype "input"))
    )
    (net (code "95") (name "unconnected-(V4F-A-Pad12)") (class "Default")
      (node (ref "V4") (pin "12") (pinfunction "A_12") (pintype "input"))
    )
    (net (code "96") (name "unconnected-(V4F-B-Pad13)") (class "Default")
      (node (ref "V4") (pin "13") (pinfunction "B_13") (pintype "input"))
    )
    (net (code "97") (name "unconnected-(V4F-Y-Pad11)") (class "Default")
      (node (ref "V4") (pin "11") (pinfunction "Y_11") (pintype "output"))
    )
    (net (code "98") (name "unconnected-(V5F-A-Pad12)") (class "Default")
      (node (ref "V5") (pin "12") (pinfunction "A_12") (pintype "input"))
    )
    (net (code "99") (name "unconnected-(V5F-B-Pad13)") (class "Default")
      (node (ref "V5") (pin "13") (pinfunction "B_13") (pintype "input"))
    )
    (net (code "100") (name "unconnected-(V5F-Y-Pad11)") (class "Default")
      (node (ref "V5") (pin "11") (pinfunction "Y_11") (pintype "output"))
    )
    (net (code "101") (name "unconnected-(V6F-A-Pad12)") (class "Default")
      (node (ref "V6") (pin "12") (pinfunction "A_12") (pintype "input"))
    )
    (net (code "102") (name "unconnected-(V6F-B-Pad13)") (class "Default")
      (node (ref "V6") (pin "13") (pinfunction "B_13") (pintype "input"))
    )
    (net (code "103") (name "unconnected-(V6F-Y-Pad11)") (class "Default")
      (node (ref "V6") (pin "11") (pinfunction "Y_11") (pintype "output"))
    )
    (net (code "104") (name "unconnected-(V7F-A-Pad12)") (class "Default")
      (node (ref "V7") (pin "12") (pinfunction "A_12") (pintype "input"))
    )
    (net (code "105") (name "unconnected-(V7F-B-Pad13)") (class "Default")
      (node (ref "V7") (pin "13") (pinfunction "B_13") (pintype "input"))
    )
    (net (code "106") (name "unconnected-(V7F-Y-Pad11)") (class "Default")
      (node (ref "V7") (pin "11") (pinfunction "Y_11") (pintype "output"))
    )
    (net (code "107") (name "unconnected-(V8F-A-Pad12)") (class "Default")
      (node (ref "V8") (pin "12") (pinfunction "A_12") (pintype "input"))
    )
    (net (code "108") (name "unconnected-(V8F-B-Pad13)") (class "Default")
      (node (ref "V8") (pin "13") (pinfunction "B_13") (pintype "input"))
    )
    (net (code "109") (name "unconnected-(V8F-Y-Pad11)") (class "Default")
      (node (ref "V8") (pin "11") (pinfunction "Y_11") (pintype "output"))
    )
    (net (code "110") (name "unconnected-(V9E-A-Pad9)") (class "Default")
      (node (ref "V9") (pin "9") (pinfunction "A_9") (pintype "input"))
    )
    (net (code "111") (name "unconnected-(V9E-B-Pad10)") (class "Default")
      (node (ref "V9") (pin "10") (pinfunction "B_10") (pintype "input"))
    )
    (net (code "112") (name "unconnected-(V9E-Y-Pad8)") (class "Default")
      (node (ref "V9") (pin "8") (pinfunction "Y_8") (pintype "output"))
    )
    (net (code "113") (name "unconnected-(V9F-A-Pad12)") (class "Default")
      (node (ref "V9") (pin "12") (pinfunction "A_12") (pintype "input"))
    )
    (net (code "114") (name "unconnected-(V9F-B-Pad13)") (class "Default")
      (node (ref "V9") (pin "13") (pinfunction "B_13") (pintype "input"))
    )
    (net (code "115") (name "unconnected-(V9F-Y-Pad11)") (class "Default")
      (node (ref "V9") (pin "11") (pinfunction "Y_11") (pintype "output"))
    )
    (net (code "116") (name "unconnected-(V11E-A-Pad9)") (class "Default")
      (node (ref "V11") (pin "9") (pinfunction "A_9") (pintype "input"))
    )
    (net (code "117") (name "unconnected-(V11E-B-Pad10)") (class "Default")
      (node (ref "V11") (pin "10") (pinfunction "B_10") (pintype "input"))
    )
    (net (code "118") (name "unconnected-(V11E-Y-Pad8)") (class "Default")
      (node (ref "V11") (pin "8") (pinfunction "Y_8") (pintype "output"))
    )
    (net (code "119") (name "unconnected-(V11F-A-Pad12)") (class "Default")
      (node (ref "V11") (pin "12") (pinfunction "A_12") (pintype "input"))
    )
    (net (code "120") (name "unconnected-(V11F-B-Pad13)") (class "Default")
      (node (ref "V11") (pin "13") (pinfunction "B_13") (pintype "input"))
    )
    (net (code "121") (name "unconnected-(V11F-Y-Pad11)") (class "Default")
      (node (ref "V11") (pin "11") (pinfunction "Y_11") (pintype "output"))
    )
    (net (code "122") (name "unconnected-(V14F-A-Pad12)") (class "Default")
      (node (ref "V14") (pin "12") (pinfunction "A_12") (pintype "input"))
    )
    (net (code "123") (name "unconnected-(V14F-B-Pad13)") (class "Default")
      (node (ref "V14") (pin "13") (pinfunction "B_13") (pintype "input"))
    )
    (net (code "124") (name "unconnected-(V14F-Y-Pad11)") (class "Default")
      (node (ref "V14") (pin "11") (pinfunction "Y_11") (pintype "output"))
    )
  )
)
